# Toilet_Assistance.net
KiCad netlist of a schematic drawn in EasyEDA
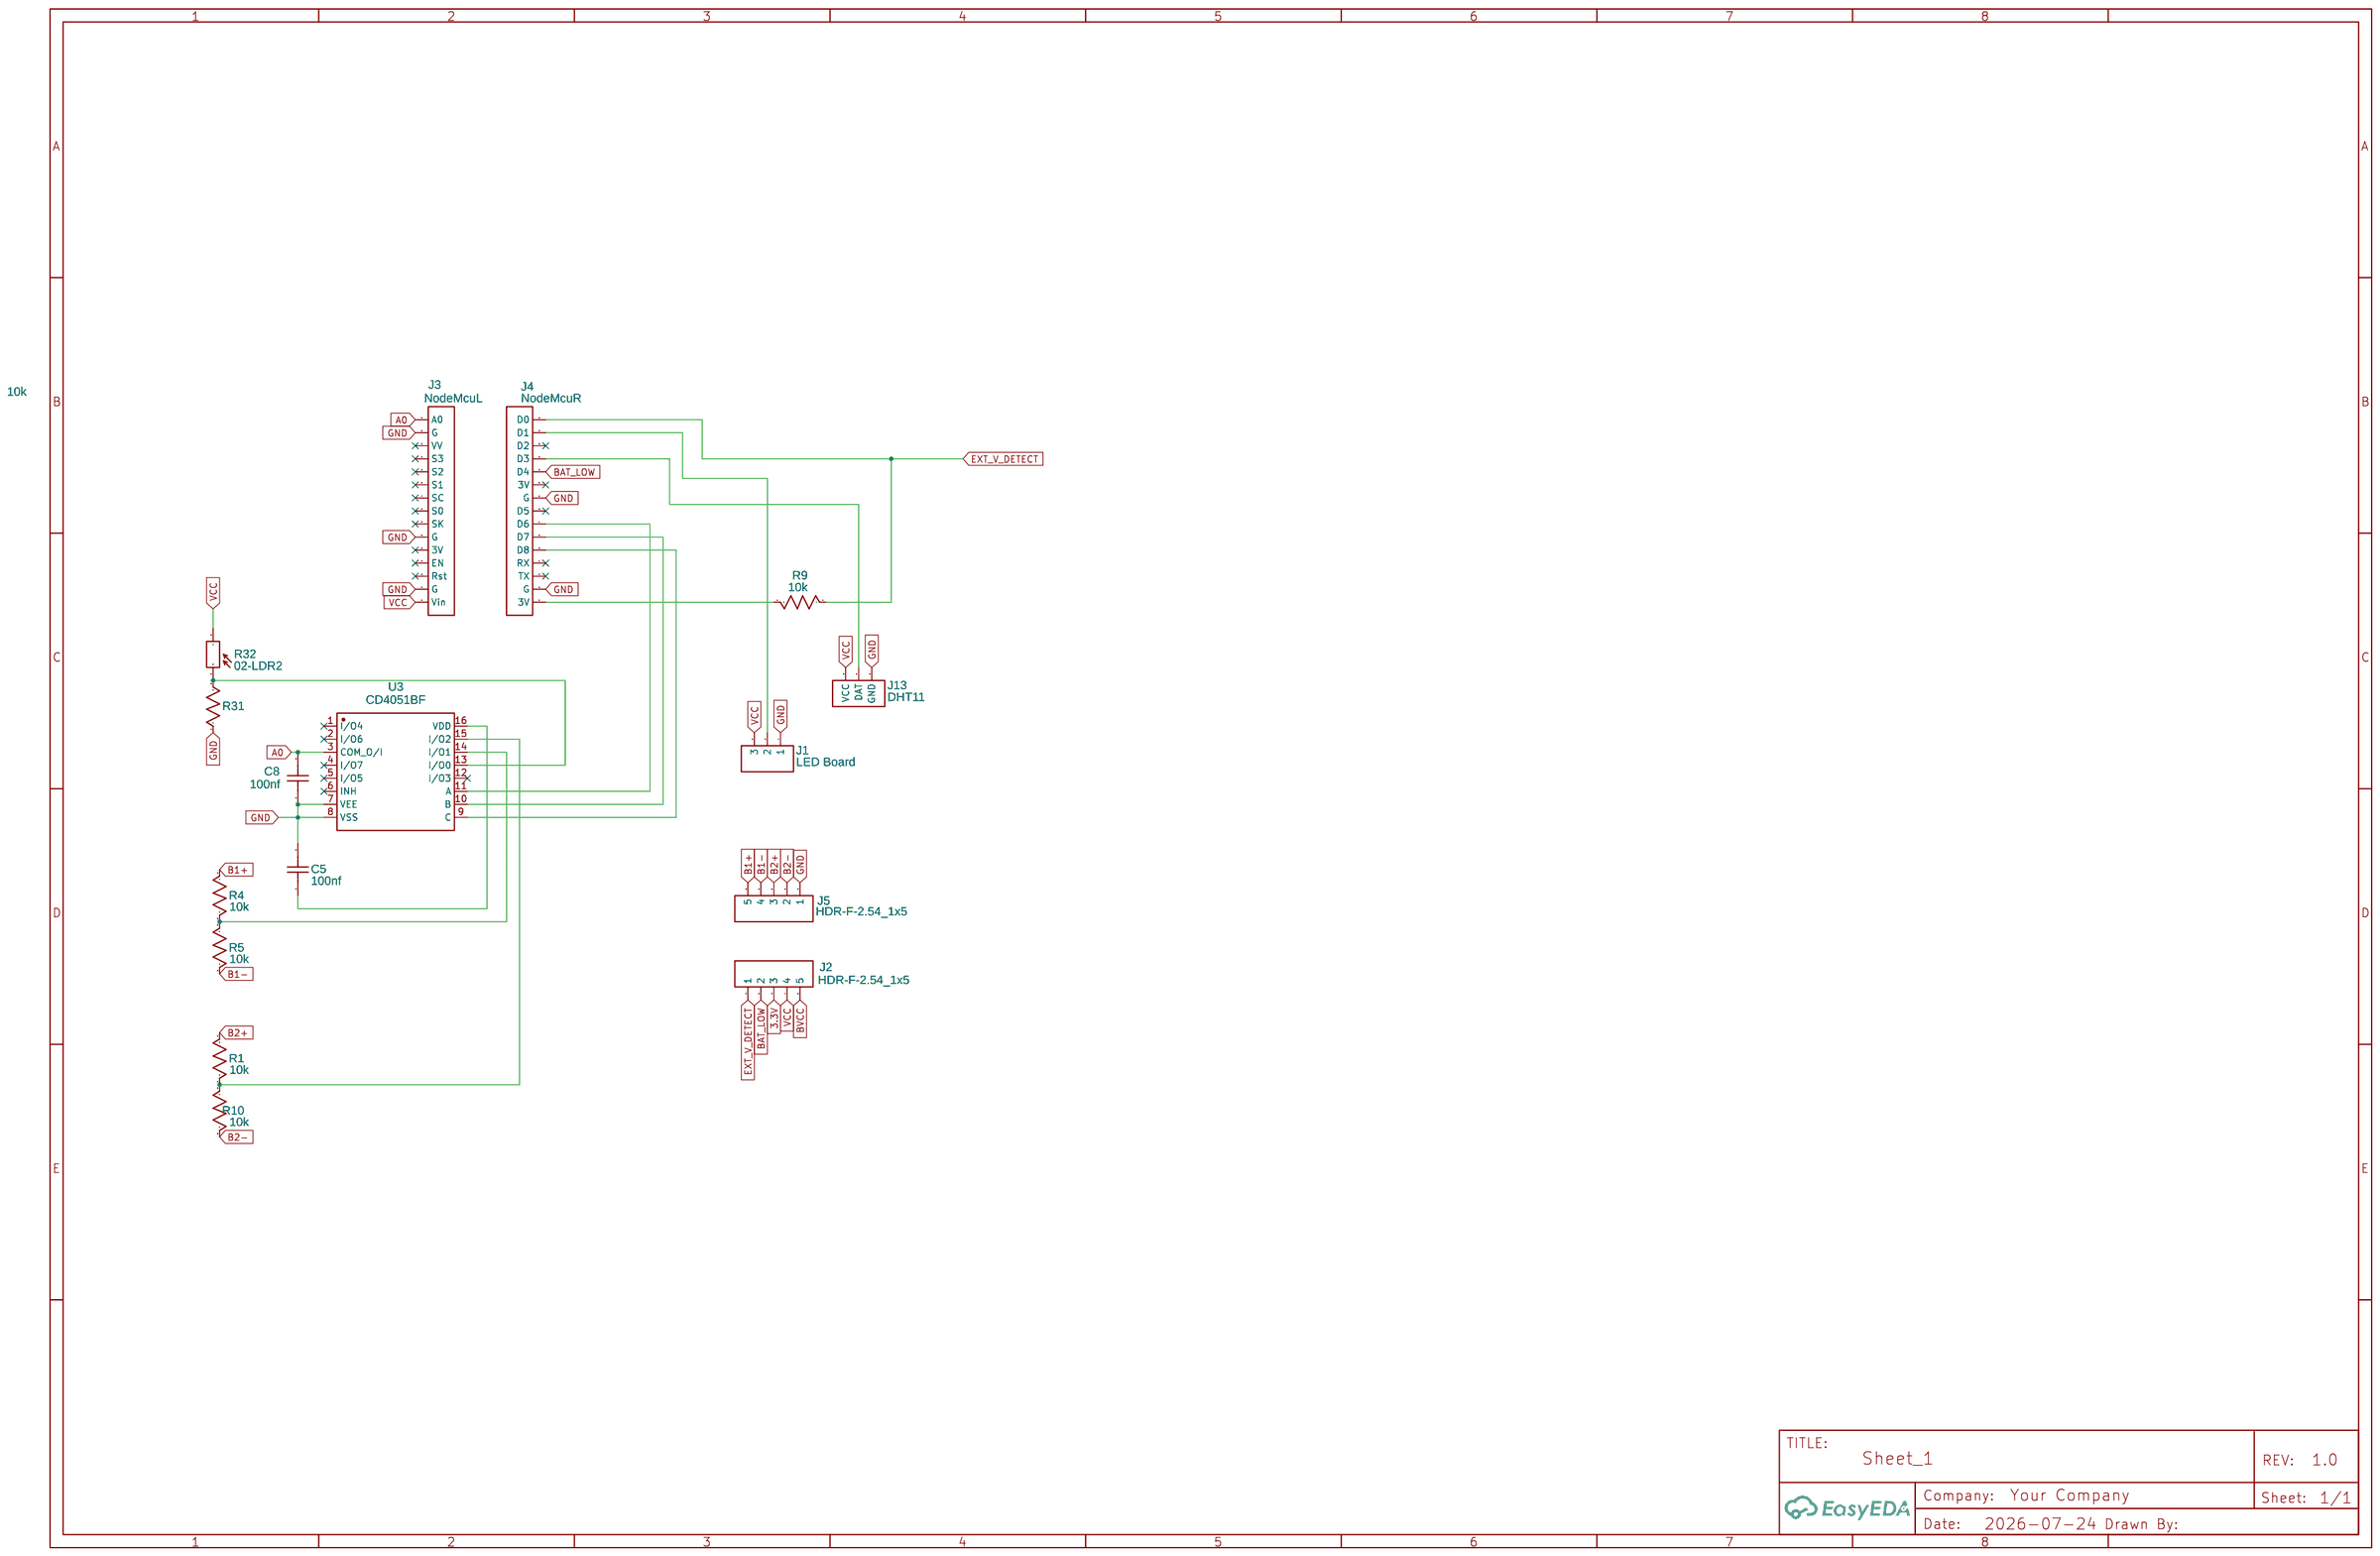
[diagram p0: schematic sheet]

(export (version "E")
  (design (tool "Eeschema 10.0.6"))
  (components
    (comp (ref "C5") (value "100nf") (libsource (lib "") (part "C_RAD-0.1_US")))
    (comp (ref "C8") (value "100nf") (libsource (lib "") (part "C_RAD-0.1_US")))
    (comp (ref "J1") (value "LED Board") (libsource (lib "") (part "HDR-M-2.54_1x3")))
    (comp (ref "J2") (value "HDR-F-2.54_1x5") (libsource (lib "") (part "HDR-M-2.54_1x5_1")))
    (comp (ref "J3") (value "NodeMcuL") (libsource (lib "") (part "HDR-M-2.54_1x15")))
    (comp (ref "J4") (value "NodeMcuR") (libsource (lib "") (part "HDR-M-2.54_1x15_1")))
    (comp (ref "J5") (value "HDR-F-2.54_1x5") (libsource (lib "") (part "HDR-M-2.54_1x5")))
    (comp (ref "J13") (value "DHT11") (libsource (lib "") (part "HDR-M-2.54_1x3_1")))
    (comp (ref "R1") (value "10k") (libsource (lib "") (part "R_AXIAL-0.3_US")))
    (comp (ref "R4") (value "10k") (libsource (lib "") (part "R_AXIAL-0.3_US")))
    (comp (ref "R5") (value "10k") (libsource (lib "") (part "R_AXIAL-0.3_US")))
    (comp (ref "R9") (value "10k") (libsource (lib "") (part "R_AXIAL-0.3_US_1")))
    (comp (ref "R10") (value "10k") (libsource (lib "") (part "R_AXIAL-0.3_US")))
    (comp (ref "R31") (value "10k") (libsource (lib "") (part "R_AXIAL-0.3_US_2")))
    (comp (ref "R32")
      (value "02-LDR2")
      (fields (field (name "Manufacturer") "NTE Electronics"))
      (libsource (lib "") (part "02-LDR2"))
    )
    (comp (ref "U3")
      (value "CD4051BF")
      (fields (field (name "Manufacturer") "TI(德州仪器)"))
      (libsource (lib "") (part "CD4051BF"))
    )
  )
  (nets
    (net (code "1") (name "3.3V") (class "Default")
      (node (ref "J2") (pin "3") (pinfunction "3_3") (pintype "unspecified"))
    )
    (net (code "2") (name "A0") (class "Default")
      (node (ref "C8") (pin "1") (pinfunction "1_1") (pintype "unspecified"))
      (node (ref "J3") (pin "1") (pinfunction "A0_1") (pintype "unspecified"))
      (node (ref "U3") (pin "3") (pinfunction "COM_O/I_3") (pintype "unspecified"))
    )
    (net (code "3") (name "B1+") (class "Default")
      (node (ref "J5") (pin "5") (pinfunction "5_5") (pintype "unspecified"))
      (node (ref "R4") (pin "1") (pinfunction "1_1") (pintype "unspecified"))
    )
    (net (code "4") (name "B1-") (class "Default")
      (node (ref "J5") (pin "4") (pinfunction "4_4") (pintype "unspecified"))
      (node (ref "R5") (pin "2") (pinfunction "2_2") (pintype "unspecified"))
    )
    (net (code "5") (name "B2+") (class "Default")
      (node (ref "J5") (pin "3") (pinfunction "3_3") (pintype "unspecified"))
      (node (ref "R1") (pin "1") (pinfunction "1_1") (pintype "unspecified"))
    )
    (net (code "6") (name "B2-") (class "Default")
      (node (ref "J5") (pin "2") (pinfunction "2_2") (pintype "unspecified"))
      (node (ref "R10") (pin "2") (pinfunction "2_2") (pintype "unspecified"))
    )
    (net (code "7") (name "BAT_LOW") (class "Default")
      (node (ref "J2") (pin "2") (pinfunction "2_2") (pintype "unspecified"))
      (node (ref "J4") (pin "11") (pinfunction "D4_11") (pintype "unspecified"))
    )
    (net (code "8") (name "BVCC") (class "Default")
      (node (ref "J2") (pin "5") (pinfunction "5_5") (pintype "unspecified"))
    )
    (net (code "9") (name "EXT_V_DETECT") (class "Default")
      (node (ref "J2") (pin "1") (pinfunction "1_1") (pintype "unspecified"))
      (node (ref "J4") (pin "15") (pinfunction "D0_15") (pintype "unspecified"))
      (node (ref "R9") (pin "1") (pinfunction "1_1") (pintype "unspecified"))
    )
    (net (code "10") (name "GND") (class "Default")
      (node (ref "C5") (pin "1") (pinfunction "1_1") (pintype "unspecified"))
      (node (ref "C8") (pin "2") (pinfunction "2_2") (pintype "unspecified"))
      (node (ref "J1") (pin "1") (pinfunction "1_1") (pintype "input"))
      (node (ref "J13") (pin "1") (pinfunction "GND_1") (pintype "input"))
      (node (ref "J3") (pin "10") (pinfunction "G_10") (pintype "unspecified"))
      (node (ref "J3") (pin "14") (pinfunction "G_14") (pintype "unspecified"))
      (node (ref "J3") (pin "2") (pinfunction "G_2") (pintype "unspecified"))
      (node (ref "J4") (pin "2") (pinfunction "G_2") (pintype "unspecified"))
      (node (ref "J4") (pin "9") (pinfunction "G_9") (pintype "unspecified"))
      (node (ref "J5") (pin "1") (pinfunction "1_1") (pintype "unspecified"))
      (node (ref "R31") (pin "1") (pinfunction "1_1") (pintype "unspecified"))
      (node (ref "U3") (pin "7") (pinfunction "VEE_7") (pintype "unspecified"))
      (node (ref "U3") (pin "8") (pinfunction "VSS_8") (pintype "unspecified"))
    )
    (net (code "11") (name "Net-(J4-3V-Pad1)") (class "Default")
      (node (ref "J4") (pin "1") (pinfunction "3V_1") (pintype "unspecified"))
      (node (ref "R9") (pin "2") (pinfunction "2_2") (pintype "unspecified"))
    )
    (net (code "12") (name "Net-(J4-D1)") (class "Default")
      (node (ref "J1") (pin "2") (pinfunction "2_2") (pintype "input"))
      (node (ref "J4") (pin "14") (pinfunction "D1_14") (pintype "unspecified"))
    )
    (net (code "13") (name "Net-(J4-D6)") (class "Default")
      (node (ref "J4") (pin "7") (pinfunction "D6_7") (pintype "unspecified"))
      (node (ref "U3") (pin "11") (pinfunction "A_11") (pintype "unspecified"))
    )
    (net (code "14") (name "Net-(J4-D7)") (class "Default")
      (node (ref "J4") (pin "6") (pinfunction "D7_6") (pintype "unspecified"))
      (node (ref "U3") (pin "10") (pinfunction "B_10") (pintype "unspecified"))
    )
    (net (code "15") (name "Net-(J4-D8)") (class "Default")
      (node (ref "J4") (pin "5") (pinfunction "D8_5") (pintype "unspecified"))
      (node (ref "U3") (pin "9") (pinfunction "C_9") (pintype "unspecified"))
    )
    (net (code "16") (name "Net-(J13-DAT)") (class "Default")
      (node (ref "J13") (pin "2") (pinfunction "DAT_2") (pintype "input"))
      (node (ref "J4") (pin "12") (pinfunction "D3_12") (pintype "unspecified"))
    )
    (net (code "17") (name "Net-(U3-I{slash}O0)") (class "Default")
      (node (ref "R31") (pin "2") (pinfunction "2_2") (pintype "unspecified"))
      (node (ref "R32") (pin "2") (pinfunction "2_2") (pintype "unspecified"))
      (node (ref "U3") (pin "13") (pinfunction "I/O0_13") (pintype "unspecified"))
    )
    (net (code "18") (name "Net-(U3-I{slash}O1)") (class "Default")
      (node (ref "R4") (pin "2") (pinfunction "2_2") (pintype "unspecified"))
      (node (ref "R5") (pin "1") (pinfunction "1_1") (pintype "unspecified"))
      (node (ref "U3") (pin "14") (pinfunction "I/O1_14") (pintype "unspecified"))
    )
    (net (code "19") (name "Net-(U3-I{slash}O2)") (class "Default")
      (node (ref "R1") (pin "2") (pinfunction "2_2") (pintype "unspecified"))
      (node (ref "R10") (pin "1") (pinfunction "1_1") (pintype "unspecified"))
      (node (ref "U3") (pin "15") (pinfunction "I/O2_15") (pintype "unspecified"))
    )
    (net (code "20") (name "Net-(U3-VDD)") (class "Default")
      (node (ref "C5") (pin "2") (pinfunction "2_2") (pintype "unspecified"))
      (node (ref "U3") (pin "16") (pinfunction "VDD_16") (pintype "unspecified"))
    )
    (net (code "21") (name "VCC") (class "Default")
      (node (ref "J1") (pin "3") (pinfunction "3_3") (pintype "input"))
      (node (ref "J13") (pin "3") (pinfunction "VCC_3") (pintype "input"))
      (node (ref "J2") (pin "4") (pinfunction "4_4") (pintype "unspecified"))
      (node (ref "J3") (pin "15") (pinfunction "Vin_15") (pintype "unspecified"))
      (node (ref "R32") (pin "1") (pinfunction "1_1") (pintype "unspecified"))
    )
    (net (code "22") (name "unconnected-(J3-3V-Pad11)") (class "Default")
      (node (ref "J3") (pin "11") (pinfunction "3V_11") (pintype "unspecified+no_connect"))
    )
    (net (code "23") (name "unconnected-(J3-EN-Pad12)") (class "Default")
      (node (ref "J3") (pin "12") (pinfunction "EN_12") (pintype "unspecified+no_connect"))
    )
    (net (code "24") (name "unconnected-(J3-Rst-Pad13)") (class "Default")
      (node (ref "J3") (pin "13") (pinfunction "Rst_13") (pintype "unspecified+no_connect"))
    )
    (net (code "25") (name "unconnected-(J3-S0-Pad8)") (class "Default")
      (node (ref "J3") (pin "8") (pinfunction "S0_8") (pintype "unspecified+no_connect"))
    )
    (net (code "26") (name "unconnected-(J3-S1-Pad6)") (class "Default")
      (node (ref "J3") (pin "6") (pinfunction "S1_6") (pintype "unspecified+no_connect"))
    )
    (net (code "27") (name "unconnected-(J3-S2-Pad5)") (class "Default")
      (node (ref "J3") (pin "5") (pinfunction "S2_5") (pintype "unspecified+no_connect"))
    )
    (net (code "28") (name "unconnected-(J3-S3-Pad4)") (class "Default")
      (node (ref "J3") (pin "4") (pinfunction "S3_4") (pintype "unspecified+no_connect"))
    )
    (net (code "29") (name "unconnected-(J3-SC-Pad7)") (class "Default")
      (node (ref "J3") (pin "7") (pinfunction "SC_7") (pintype "unspecified+no_connect"))
    )
    (net (code "30") (name "unconnected-(J3-SK-Pad9)") (class "Default")
      (node (ref "J3") (pin "9") (pinfunction "SK_9") (pintype "unspecified+no_connect"))
    )
    (net (code "31") (name "unconnected-(J3-VV-Pad3)") (class "Default")
      (node (ref "J3") (pin "3") (pinfunction "VV_3") (pintype "unspecified+no_connect"))
    )
    (net (code "32") (name "unconnected-(J4-3V-Pad10)") (class "Default")
      (node (ref "J4") (pin "10") (pinfunction "3V_10") (pintype "unspecified+no_connect"))
    )
    (net (code "33") (name "unconnected-(J4-D2-Pad13)") (class "Default")
      (node (ref "J4") (pin "13") (pinfunction "D2_13") (pintype "unspecified+no_connect"))
    )
    (net (code "34") (name "unconnected-(J4-D5-Pad8)") (class "Default")
      (node (ref "J4") (pin "8") (pinfunction "D5_8") (pintype "unspecified+no_connect"))
    )
    (net (code "35") (name "unconnected-(J4-RX-Pad4)") (class "Default")
      (node (ref "J4") (pin "4") (pinfunction "RX_4") (pintype "unspecified+no_connect"))
    )
    (net (code "36") (name "unconnected-(J4-TX-Pad3)") (class "Default")
      (node (ref "J4") (pin "3") (pinfunction "TX_3") (pintype "unspecified+no_connect"))
    )
    (net (code "37") (name "unconnected-(U3-INH-Pad6)") (class "Default")
      (node (ref "U3") (pin "6") (pinfunction "INH_6") (pintype "unspecified+no_connect"))
    )
    (net (code "38") (name "unconnected-(U3-I{slash}O3-Pad12)") (class "Default")
      (node (ref "U3") (pin "12") (pinfunction "I/O3_12") (pintype "unspecified+no_connect"))
    )
    (net (code "39") (name "unconnected-(U3-I{slash}O4-Pad1)") (class "Default")
      (node (ref "U3") (pin "1") (pinfunction "I/O4_1") (pintype "unspecified+no_connect"))
    )
    (net (code "40") (name "unconnected-(U3-I{slash}O5-Pad5)") (class "Default")
      (node (ref "U3") (pin "5") (pinfunction "I/O5_5") (pintype "unspecified+no_connect"))
    )
    (net (code "41") (name "unconnected-(U3-I{slash}O6-Pad2)") (class "Default")
      (node (ref "U3") (pin "2") (pinfunction "I/O6_2") (pintype "unspecified+no_connect"))
    )
    (net (code "42") (name "unconnected-(U3-I{slash}O7-Pad4)") (class "Default")
      (node (ref "U3") (pin "4") (pinfunction "I/O7_4") (pintype "unspecified+no_connect"))
    )
  )
)
